# logger.net
KiCad netlist of a schematic drawn in EAGLE
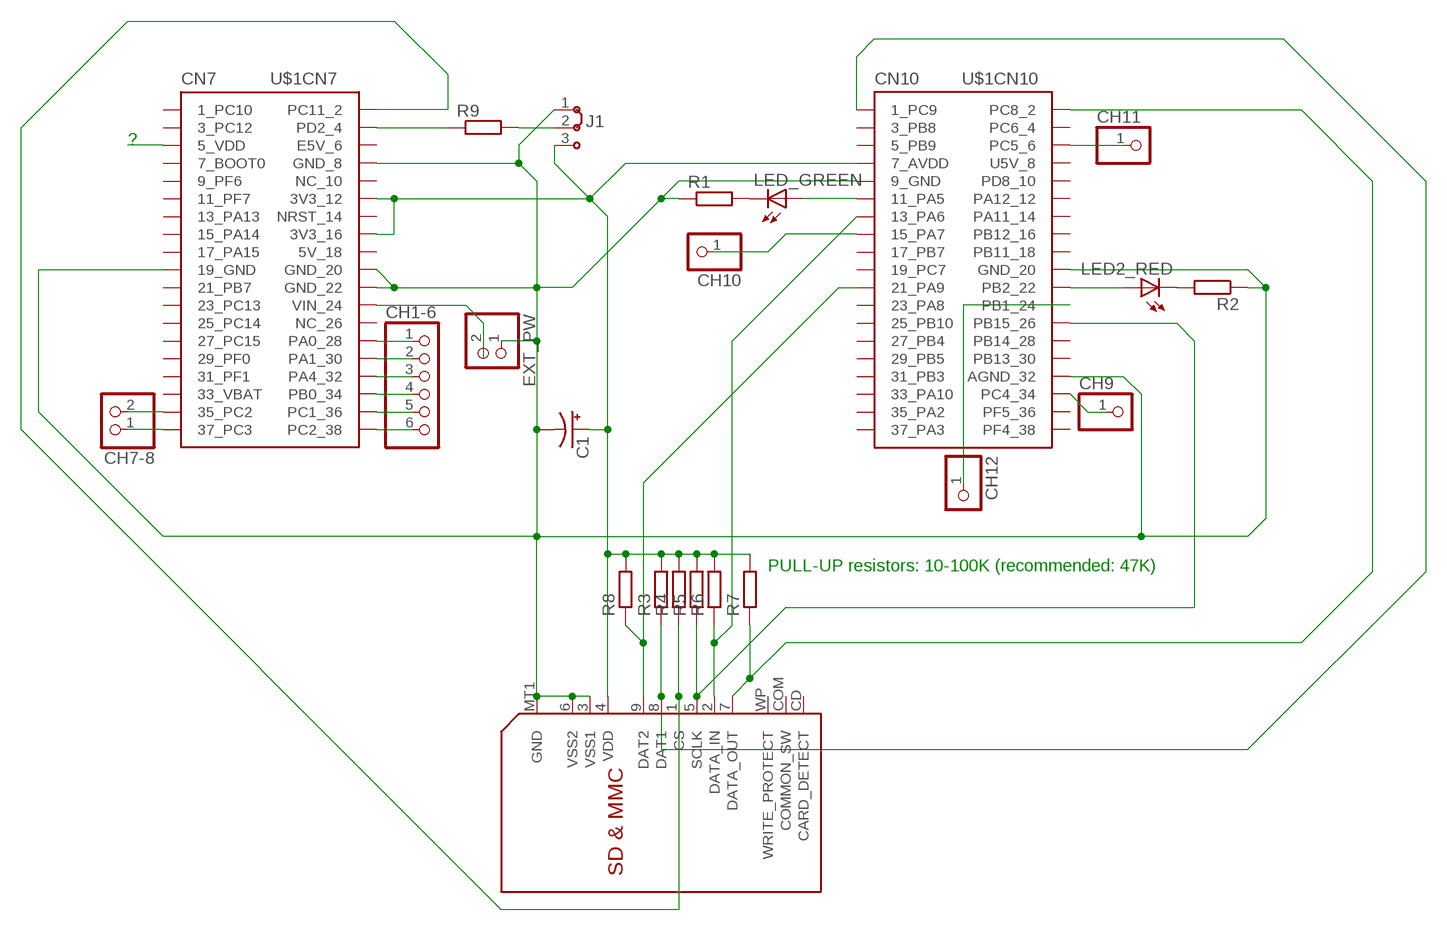
[diagram p0: schematic, sheet 1]

(export (version "E")
  (design (tool "Eeschema 10.0.6"))
  (components
    (comp (ref "C1")
      (value "CPOL-USE5-10.5")
      (footprint "eagle-import:E5-10,5")
      (libsource (lib "eagle-import") (part "CPOL-USE5-10.5"))
    )
    (comp (ref "CH1-6")
      (value "PINHD-1X6B")
      (footprint "eagle-import:1X06-BIG")
      (libsource (lib "eagle-import") (part "PINHD-1X6B"))
    )
    (comp (ref "CH7-8")
      (value "PINHD-1X2")
      (footprint "eagle-import:1X02")
      (libsource (lib "eagle-import") (part "PINHD-1X2"))
    )
    (comp (ref "CH9")
      (value "PINHD-1X1")
      (footprint "eagle-import:1X01")
      (libsource (lib "eagle-import") (part "PINHD-1X1"))
    )
    (comp (ref "CH10")
      (value "PINHD-1X1")
      (footprint "eagle-import:1X01")
      (libsource (lib "eagle-import") (part "PINHD-1X1"))
    )
    (comp (ref "CH11")
      (value "PINHD-1X1")
      (footprint "eagle-import:1X01")
      (libsource (lib "eagle-import") (part "PINHD-1X1"))
    )
    (comp (ref "CH12")
      (value "PINHD-1X1")
      (footprint "eagle-import:1X01")
      (libsource (lib "eagle-import") (part "PINHD-1X1"))
    )
    (comp (ref "EXT_PW")
      (value "PINHD-1X2")
      (footprint "eagle-import:1X02")
      (libsource (lib "eagle-import") (part "PINHD-1X2"))
    )
    (comp (ref "J1")
      (value "J2X2MM")
      (footprint "eagle-import:04C")
      (libsource (lib "eagle-import") (part "J2X2MM"))
    )
    (comp (ref "LED2_RED")
      (value "LED")
      (footprint "eagle-import:SMARTLED-TTW")
      (libsource (lib "eagle-import") (part "LED"))
    )
    (comp (ref "LED_GREEN")
      (value "LED")
      (footprint "eagle-import:SMARTLED-TTW")
      (libsource (lib "eagle-import") (part "LED"))
    )
    (comp (ref "R1")
      (value "R-EU_M3216")
      (footprint "eagle-import:M3216")
      (libsource (lib "eagle-import") (part "R-EU_M3216"))
    )
    (comp (ref "R2")
      (value "R-EU_M3216")
      (footprint "eagle-import:M3216")
      (libsource (lib "eagle-import") (part "R-EU_M3216"))
    )
    (comp (ref "R3")
      (value "R-EU_M3216")
      (footprint "eagle-import:M3216")
      (libsource (lib "eagle-import") (part "R-EU_M3216"))
    )
    (comp (ref "R4")
      (value "R-EU_M3216")
      (footprint "eagle-import:M3216")
      (libsource (lib "eagle-import") (part "R-EU_M3216"))
    )
    (comp (ref "R5")
      (value "R-EU_M3216")
      (footprint "eagle-import:M3216")
      (libsource (lib "eagle-import") (part "R-EU_M3216"))
    )
    (comp (ref "R6")
      (value "R-EU_M3216")
      (footprint "eagle-import:M3216")
      (libsource (lib "eagle-import") (part "R-EU_M3216"))
    )
    (comp (ref "R7")
      (value "R-EU_M3216")
      (footprint "eagle-import:M3216")
      (libsource (lib "eagle-import") (part "R-EU_M3216"))
    )
    (comp (ref "R8")
      (value "R-EU_M3216")
      (footprint "eagle-import:M3216")
      (libsource (lib "eagle-import") (part "R-EU_M3216"))
    )
    (comp (ref "R9")
      (value "R-EU_M3216")
      (footprint "eagle-import:M3216")
      (libsource (lib "eagle-import") (part "R-EU_M3216"))
    )
    (comp (ref "U$1")
      (value "NUCLEO-SHIELD-FULLSIZE")
      (footprint "eagle-import:NUCLEO-SHIELD-WITHHOLES-FULLSIZE")
      (libsource (lib "eagle-import") (part "NUCLEO-SHIELD-FULLSIZE"))
    )
    (comp (ref "U$2")
      (value "SDMMC18650")
      (footprint "eagle-import:SDCARD")
      (libsource (lib "eagle-import") (part "SDMMC18650"))
    )
  )
  (nets
    (net (code "1") (name "Net-(J1-Pad2)") (class "Default")
      (node (ref "J1") (pin "2") (pinfunction "2_2") (pintype "passive"))
      (node (ref "R9") (pin "2") (pinfunction "2_2") (pintype "passive"))
    )
    (net (code "2") (name "Net-(LED2_RED-A)") (class "Default")
      (node (ref "LED2_RED") (pin "A@1") (pinfunction "A_A@1") (pintype "passive"))
      (node (ref "U$1") (pin "CN10_22") (pinfunction "PB2_22_CN10_22") (pintype "bidirectional"))
    )
    (net (code "3") (name "Net-(LED2_RED-C)") (class "Default")
      (node (ref "LED2_RED") (pin "C@1") (pinfunction "C_C@1") (pintype "passive"))
      (node (ref "R2") (pin "2") (pinfunction "2_2") (pintype "passive"))
    )
    (net (code "4") (name "Net-(LED_GREEN-A)") (class "Default")
      (node (ref "LED_GREEN") (pin "A@1") (pinfunction "A_A@1") (pintype "passive"))
      (node (ref "U$1") (pin "CN10_11") (pinfunction "11_PA5_CN10_11") (pintype "bidirectional"))
    )
    (net (code "5") (name "Net-(LED_GREEN-C)") (class "Default")
      (node (ref "LED_GREEN") (pin "C@1") (pinfunction "C_C@1") (pintype "passive"))
      (node (ref "R1") (pin "2") (pinfunction "2_2") (pintype "passive"))
    )
    (net (code "6") (name "Net-(U$1A-7_AVDD)") (class "Default")
      (node (ref "C1") (pin "+") (pinfunction "+_+") (pintype "passive"))
      (node (ref "J1") (pin "3") (pinfunction "3_3") (pintype "passive"))
      (node (ref "R3") (pin "2") (pinfunction "2_2") (pintype "passive"))
      (node (ref "R4") (pin "2") (pinfunction "2_2") (pintype "passive"))
      (node (ref "R5") (pin "2") (pinfunction "2_2") (pintype "passive"))
      (node (ref "R6") (pin "2") (pinfunction "2_2") (pintype "passive"))
      (node (ref "R7") (pin "2") (pinfunction "2_2") (pintype "passive"))
      (node (ref "R8") (pin "2") (pinfunction "2_2") (pintype "passive"))
      (node (ref "U$1") (pin "CN10_7") (pinfunction "7_AVDD_CN10_7") (pintype "bidirectional"))
      (node (ref "U$1") (pin "CN7_12") (pinfunction "3V3_12_CN7_12") (pintype "bidirectional"))
      (node (ref "U$1") (pin "CN7_16") (pinfunction "3V3_16_CN7_16") (pintype "bidirectional"))
      (node (ref "U$2") (pin "4") (pinfunction "VDD_4") (pintype "power_in"))
    )
    (net (code "7") (name "Net-(U$1A-9_GND)") (class "Default")
      (node (ref "C1") (pin "-") (pinfunction "-_-") (pintype "passive"))
      (node (ref "EXT_PW") (pin "1") (pinfunction "1_1") (pintype "passive"))
      (node (ref "J1") (pin "1") (pinfunction "1_1") (pintype "passive"))
      (node (ref "R1") (pin "1") (pinfunction "1_1") (pintype "passive"))
      (node (ref "R2") (pin "1") (pinfunction "1_1") (pintype "passive"))
      (node (ref "U$1") (pin "CN10_20") (pinfunction "GND_20_CN10_20") (pintype "bidirectional"))
      (node (ref "U$1") (pin "CN10_32") (pinfunction "AGND_32_CN10_32") (pintype "bidirectional"))
      (node (ref "U$1") (pin "CN10_9") (pinfunction "9_GND_CN10_9") (pintype "bidirectional"))
      (node (ref "U$1") (pin "CN7_19") (pinfunction "19_GND_CN7_19") (pintype "bidirectional"))
      (node (ref "U$1") (pin "CN7_20") (pinfunction "GND_20_CN7_20") (pintype "bidirectional"))
      (node (ref "U$1") (pin "CN7_22") (pinfunction "GND_22_CN7_22") (pintype "bidirectional"))
      (node (ref "U$1") (pin "CN7_8") (pinfunction "GND_8_CN7_8") (pintype "bidirectional"))
      (node (ref "U$2") (pin "3") (pinfunction "VSS1_3") (pintype "power_in"))
      (node (ref "U$2") (pin "6") (pinfunction "VSS2_6") (pintype "power_in"))
      (node (ref "U$2") (pin "MT1") (pinfunction "GND_MT1") (pintype "power_in"))
    )
    (net (code "8") (name "Net-(U$1A-13_PA6)") (class "Default")
      (node (ref "R6") (pin "1") (pinfunction "1_1") (pintype "passive"))
      (node (ref "U$1") (pin "CN10_13") (pinfunction "13_PA6_CN10_13") (pintype "bidirectional"))
      (node (ref "U$2") (pin "2") (pinfunction "DATA_IN_2") (pintype "input"))
    )
    (net (code "9") (name "Net-(U$1A-15_PA7)") (class "Default")
      (node (ref "CH10") (pin "1") (pinfunction "1_1") (pintype "passive"))
      (node (ref "U$1") (pin "CN10_15") (pinfunction "15_PA7_CN10_15") (pintype "bidirectional"))
    )
    (net (code "10") (name "Net-(U$1A-21_PA9)") (class "Default")
      (node (ref "R8") (pin "1") (pinfunction "1_1") (pintype "passive"))
      (node (ref "U$1") (pin "CN10_21") (pinfunction "21_PA9_CN10_21") (pintype "bidirectional"))
      (node (ref "U$2") (pin "9") (pinfunction "DAT2_9") (pintype "bidirectional"))
    )
    (net (code "11") (name "Net-(U$1A-PB1_24)") (class "Default")
      (node (ref "CH12") (pin "1") (pinfunction "1_1") (pintype "passive"))
      (node (ref "U$1") (pin "CN10_24") (pinfunction "PB1_24_CN10_24") (pintype "bidirectional"))
    )
    (net (code "12") (name "Net-(U$1A-PB15_26)") (class "Default")
      (node (ref "R5") (pin "1") (pinfunction "1_1") (pintype "passive"))
      (node (ref "U$1") (pin "CN10_26") (pinfunction "PB15_26_CN10_26") (pintype "bidirectional"))
      (node (ref "U$2") (pin "5") (pinfunction "SCLK_5") (pintype "input"))
    )
    (net (code "13") (name "Net-(U$1A-PC4_34)") (class "Default")
      (node (ref "CH9") (pin "1") (pinfunction "1_1") (pintype "passive"))
      (node (ref "U$1") (pin "CN10_34") (pinfunction "PC4_34_CN10_34") (pintype "bidirectional"))
    )
    (net (code "14") (name "Net-(U$1A-PC5_6)") (class "Default")
      (node (ref "CH11") (pin "1") (pinfunction "1_1") (pintype "passive"))
      (node (ref "U$1") (pin "CN10_6") (pinfunction "PC5_6_CN10_6") (pintype "bidirectional"))
    )
    (net (code "15") (name "Net-(U$1A-PC8_2)") (class "Default")
      (node (ref "R7") (pin "1") (pinfunction "1_1") (pintype "passive"))
      (node (ref "U$1") (pin "CN10_2") (pinfunction "PC8_2_CN10_2") (pintype "bidirectional"))
      (node (ref "U$2") (pin "7") (pinfunction "DATA_OUT_7") (pintype "output"))
    )
    (net (code "16") (name "Net-(U$1B-35_PC2)") (class "Default")
      (node (ref "CH7-8") (pin "2") (pinfunction "2_2") (pintype "passive"))
      (node (ref "U$1") (pin "CN7_35") (pinfunction "35_PC2_CN7_35") (pintype "bidirectional"))
    )
    (net (code "17") (name "Net-(U$1B-37_PC3)") (class "Default")
      (node (ref "CH7-8") (pin "1") (pinfunction "1_1") (pintype "passive"))
      (node (ref "U$1") (pin "CN7_37") (pinfunction "37_PC3_CN7_37") (pintype "bidirectional"))
    )
    (net (code "18") (name "Net-(U$1B-PA0_28)") (class "Default")
      (node (ref "CH1-6") (pin "1") (pinfunction "1_1") (pintype "passive"))
      (node (ref "U$1") (pin "CN7_28") (pinfunction "PA0_28_CN7_28") (pintype "bidirectional"))
    )
    (net (code "19") (name "Net-(U$1B-PA1_30)") (class "Default")
      (node (ref "CH1-6") (pin "2") (pinfunction "2_2") (pintype "passive"))
      (node (ref "U$1") (pin "CN7_30") (pinfunction "PA1_30_CN7_30") (pintype "bidirectional"))
    )
    (net (code "20") (name "Net-(U$1B-PA4_32)") (class "Default")
      (node (ref "CH1-6") (pin "3") (pinfunction "3_3") (pintype "passive"))
      (node (ref "U$1") (pin "CN7_32") (pinfunction "PA4_32_CN7_32") (pintype "bidirectional"))
    )
    (net (code "21") (name "Net-(U$1B-PB0_34)") (class "Default")
      (node (ref "CH1-6") (pin "4") (pinfunction "4_4") (pintype "passive"))
      (node (ref "U$1") (pin "CN7_34") (pinfunction "PB0_34_CN7_34") (pintype "bidirectional"))
    )
    (net (code "22") (name "Net-(U$1B-PC1_36)") (class "Default")
      (node (ref "CH1-6") (pin "5") (pinfunction "5_5") (pintype "passive"))
      (node (ref "U$1") (pin "CN7_36") (pinfunction "PC1_36_CN7_36") (pintype "bidirectional"))
    )
    (net (code "23") (name "Net-(U$1B-PC2_38)") (class "Default")
      (node (ref "CH1-6") (pin "6") (pinfunction "6_6") (pintype "passive"))
      (node (ref "U$1") (pin "CN7_38") (pinfunction "PC2_38_CN7_38") (pintype "bidirectional"))
    )
    (net (code "24") (name "Net-(U$1B-PC11_2)") (class "Default")
      (node (ref "R4") (pin "1") (pinfunction "1_1") (pintype "passive"))
      (node (ref "U$1") (pin "CN7_2") (pinfunction "PC11_2_CN7_2") (pintype "bidirectional"))
      (node (ref "U$2") (pin "1") (pinfunction "CS_1") (pintype "input"))
    )
    (net (code "25") (name "Net-(U$1B-PD2_4)") (class "Default")
      (node (ref "R9") (pin "1") (pinfunction "1_1") (pintype "passive"))
      (node (ref "U$1") (pin "CN7_4") (pinfunction "PD2_4_CN7_4") (pintype "bidirectional"))
    )
    (net (code "26") (name "Net-(U$2-DAT1)") (class "Default")
      (node (ref "R3") (pin "1") (pinfunction "1_1") (pintype "passive"))
      (node (ref "U$2") (pin "8") (pinfunction "DAT1_8") (pintype "bidirectional"))
    )
    (net (code "27") (name "unconnected-(EXT_PW-Pad2)") (class "Default")
      (node (ref "EXT_PW") (pin "2") (pinfunction "2_2") (pintype "passive"))
    )
    (net (code "28") (name "unconnected-(U$1A-1_PC9-PadCN10_1)") (class "Default")
      (node (ref "U$1") (pin "CN10_1") (pinfunction "1_PC9_CN10_1") (pintype "bidirectional"))
    )
    (net (code "29") (name "unconnected-(U$1A-3_PB8-PadCN10_3)") (class "Default")
      (node (ref "U$1") (pin "CN10_3") (pinfunction "3_PB8_CN10_3") (pintype "bidirectional"))
    )
    (net (code "30") (name "unconnected-(U$1A-5_PB9-PadCN10_5)") (class "Default")
      (node (ref "U$1") (pin "CN10_5") (pinfunction "5_PB9_CN10_5") (pintype "bidirectional"))
    )
    (net (code "31") (name "unconnected-(U$1A-17_PB7-PadCN10_17)") (class "Default")
      (node (ref "U$1") (pin "CN10_17") (pinfunction "17_PB7_CN10_17") (pintype "bidirectional"))
    )
    (net (code "32") (name "unconnected-(U$1A-19_PC7-PadCN10_19)") (class "Default")
      (node (ref "U$1") (pin "CN10_19") (pinfunction "19_PC7_CN10_19") (pintype "bidirectional"))
    )
    (net (code "33") (name "unconnected-(U$1A-23_PA8-PadCN10_23)") (class "Default")
      (node (ref "U$1") (pin "CN10_23") (pinfunction "23_PA8_CN10_23") (pintype "bidirectional"))
    )
    (net (code "34") (name "unconnected-(U$1A-25_PB10-PadCN10_25)") (class "Default")
      (node (ref "U$1") (pin "CN10_25") (pinfunction "25_PB10_CN10_25") (pintype "bidirectional"))
    )
    (net (code "35") (name "unconnected-(U$1A-27_PB4-PadCN10_27)") (class "Default")
      (node (ref "U$1") (pin "CN10_27") (pinfunction "27_PB4_CN10_27") (pintype "bidirectional"))
    )
    (net (code "36") (name "unconnected-(U$1A-29_PB5-PadCN10_29)") (class "Default")
      (node (ref "U$1") (pin "CN10_29") (pinfunction "29_PB5_CN10_29") (pintype "bidirectional"))
    )
    (net (code "37") (name "unconnected-(U$1A-31_PB3-PadCN10_31)") (class "Default")
      (node (ref "U$1") (pin "CN10_31") (pinfunction "31_PB3_CN10_31") (pintype "bidirectional"))
    )
    (net (code "38") (name "unconnected-(U$1A-33_PA10-PadCN10_33)") (class "Default")
      (node (ref "U$1") (pin "CN10_33") (pinfunction "33_PA10_CN10_33") (pintype "bidirectional"))
    )
    (net (code "39") (name "unconnected-(U$1A-35_PA2-PadCN10_35)") (class "Default")
      (node (ref "U$1") (pin "CN10_35") (pinfunction "35_PA2_CN10_35") (pintype "bidirectional"))
    )
    (net (code "40") (name "unconnected-(U$1A-37_PA3-PadCN10_37)") (class "Default")
      (node (ref "U$1") (pin "CN10_37") (pinfunction "37_PA3_CN10_37") (pintype "bidirectional"))
    )
    (net (code "41") (name "unconnected-(U$1A-PA11_14-PadCN10_14)") (class "Default")
      (node (ref "U$1") (pin "CN10_14") (pinfunction "PA11_14_CN10_14") (pintype "bidirectional"))
    )
    (net (code "42") (name "unconnected-(U$1A-PA12_12-PadCN10_12)") (class "Default")
      (node (ref "U$1") (pin "CN10_12") (pinfunction "PA12_12_CN10_12") (pintype "bidirectional"))
    )
    (net (code "43") (name "unconnected-(U$1A-PB11_18-PadCN10_18)") (class "Default")
      (node (ref "U$1") (pin "CN10_18") (pinfunction "PB11_18_CN10_18") (pintype "bidirectional"))
    )
    (net (code "44") (name "unconnected-(U$1A-PB12_16-PadCN10_16)") (class "Default")
      (node (ref "U$1") (pin "CN10_16") (pinfunction "PB12_16_CN10_16") (pintype "bidirectional"))
    )
    (net (code "45") (name "unconnected-(U$1A-PB13_30-PadCN10_30)") (class "Default")
      (node (ref "U$1") (pin "CN10_30") (pinfunction "PB13_30_CN10_30") (pintype "bidirectional"))
    )
    (net (code "46") (name "unconnected-(U$1A-PB14_28-PadCN10_28)") (class "Default")
      (node (ref "U$1") (pin "CN10_28") (pinfunction "PB14_28_CN10_28") (pintype "bidirectional"))
    )
    (net (code "47") (name "unconnected-(U$1A-PC6_4-PadCN10_4)") (class "Default")
      (node (ref "U$1") (pin "CN10_4") (pinfunction "PC6_4_CN10_4") (pintype "bidirectional"))
    )
    (net (code "48") (name "unconnected-(U$1A-PD8_10-PadCN10_10)") (class "Default")
      (node (ref "U$1") (pin "CN10_10") (pinfunction "PD8_10_CN10_10") (pintype "bidirectional"))
    )
    (net (code "49") (name "unconnected-(U$1A-PF4_38-PadCN10_38)") (class "Default")
      (node (ref "U$1") (pin "CN10_38") (pinfunction "PF4_38_CN10_38") (pintype "bidirectional"))
    )
    (net (code "50") (name "unconnected-(U$1A-PF5_36-PadCN10_36)") (class "Default")
      (node (ref "U$1") (pin "CN10_36") (pinfunction "PF5_36_CN10_36") (pintype "bidirectional"))
    )
    (net (code "51") (name "unconnected-(U$1A-U5V_8-PadCN10_8)") (class "Default")
      (node (ref "U$1") (pin "CN10_8") (pinfunction "U5V_8_CN10_8") (pintype "bidirectional"))
    )
    (net (code "52") (name "unconnected-(U$1B-1_PC10-PadCN7_1)") (class "Default")
      (node (ref "U$1") (pin "CN7_1") (pinfunction "1_PC10_CN7_1") (pintype "bidirectional"))
    )
    (net (code "53") (name "unconnected-(U$1B-3_PC12-PadCN7_3)") (class "Default")
      (node (ref "U$1") (pin "CN7_3") (pinfunction "3_PC12_CN7_3") (pintype "bidirectional"))
    )
    (net (code "54") (name "unconnected-(U$1B-5V_18-PadCN7_18)") (class "Default")
      (node (ref "U$1") (pin "CN7_18") (pinfunction "5V_18_CN7_18") (pintype "bidirectional"))
    )
    (net (code "55") (name "unconnected-(U$1B-5_VDD-PadCN7_5)") (class "Default")
      (node (ref "U$1") (pin "CN7_5") (pinfunction "5_VDD_CN7_5") (pintype "bidirectional"))
    )
    (net (code "56") (name "unconnected-(U$1B-7_BOOT0-PadCN7_7)") (class "Default")
      (node (ref "U$1") (pin "CN7_7") (pinfunction "7_BOOT0_CN7_7") (pintype "bidirectional"))
    )
    (net (code "57") (name "unconnected-(U$1B-9_PF6-PadCN7_9)") (class "Default")
      (node (ref "U$1") (pin "CN7_9") (pinfunction "9_PF6_CN7_9") (pintype "bidirectional"))
    )
    (net (code "58") (name "unconnected-(U$1B-11_PF7-PadCN7_11)") (class "Default")
      (node (ref "U$1") (pin "CN7_11") (pinfunction "11_PF7_CN7_11") (pintype "bidirectional"))
    )
    (net (code "59") (name "unconnected-(U$1B-13_PA13-PadCN7_13)") (class "Default")
      (node (ref "U$1") (pin "CN7_13") (pinfunction "13_PA13_CN7_13") (pintype "bidirectional"))
    )
    (net (code "60") (name "unconnected-(U$1B-15_PA14-PadCN7_15)") (class "Default")
      (node (ref "U$1") (pin "CN7_15") (pinfunction "15_PA14_CN7_15") (pintype "bidirectional"))
    )
    (net (code "61") (name "unconnected-(U$1B-17_PA15-PadCN7_17)") (class "Default")
      (node (ref "U$1") (pin "CN7_17") (pinfunction "17_PA15_CN7_17") (pintype "bidirectional"))
    )
    (net (code "62") (name "unconnected-(U$1B-21_PB7-PadCN7_21)") (class "Default")
      (node (ref "U$1") (pin "CN7_21") (pinfunction "21_PB7_CN7_21") (pintype "bidirectional"))
    )
    (net (code "63") (name "unconnected-(U$1B-23_PC13-PadCN7_23)") (class "Default")
      (node (ref "U$1") (pin "CN7_23") (pinfunction "23_PC13_CN7_23") (pintype "bidirectional"))
    )
    (net (code "64") (name "unconnected-(U$1B-25_PC14-PadCN7_25)") (class "Default")
      (node (ref "U$1") (pin "CN7_25") (pinfunction "25_PC14_CN7_25") (pintype "bidirectional"))
    )
    (net (code "65") (name "unconnected-(U$1B-27_PC15-PadCN7_27)") (class "Default")
      (node (ref "U$1") (pin "CN7_27") (pinfunction "27_PC15_CN7_27") (pintype "bidirectional"))
    )
    (net (code "66") (name "unconnected-(U$1B-29_PF0-PadCN7_29)") (class "Default")
      (node (ref "U$1") (pin "CN7_29") (pinfunction "29_PF0_CN7_29") (pintype "bidirectional"))
    )
    (net (code "67") (name "unconnected-(U$1B-31_PF1-PadCN7_31)") (class "Default")
      (node (ref "U$1") (pin "CN7_31") (pinfunction "31_PF1_CN7_31") (pintype "bidirectional"))
    )
    (net (code "68") (name "unconnected-(U$1B-33_VBAT-PadCN7_33)") (class "Default")
      (node (ref "U$1") (pin "CN7_33") (pinfunction "33_VBAT_CN7_33") (pintype "bidirectional"))
    )
    (net (code "69") (name "unconnected-(U$1B-E5V_6-PadCN7_6)") (class "Default")
      (node (ref "U$1") (pin "CN7_6") (pinfunction "E5V_6_CN7_6") (pintype "bidirectional"))
    )
    (net (code "70") (name "unconnected-(U$1B-NC_10-PadCN7_10)") (class "Default")
      (node (ref "U$1") (pin "CN7_10") (pinfunction "NC_10_CN7_10") (pintype "bidirectional"))
    )
    (net (code "71") (name "unconnected-(U$1B-NC_26-PadCN7_26)") (class "Default")
      (node (ref "U$1") (pin "CN7_26") (pinfunction "NC_26_CN7_26") (pintype "bidirectional"))
    )
    (net (code "72") (name "unconnected-(U$1B-NRST_14-PadCN7_14)") (class "Default")
      (node (ref "U$1") (pin "CN7_14") (pinfunction "NRST_14_CN7_14") (pintype "bidirectional"))
    )
    (net (code "73") (name "unconnected-(U$1B-VIN_24-PadCN7_24)") (class "Default")
      (node (ref "U$1") (pin "CN7_24") (pinfunction "VIN_24_CN7_24") (pintype "bidirectional"))
    )
    (net (code "74") (name "unconnected-(U$2-CARD_DETECT-PadCD)") (class "Default")
      (node (ref "U$2") (pin "CD") (pinfunction "CARD_DETECT_CD") (pintype "passive"))
    )
    (net (code "75") (name "unconnected-(U$2-COMMON_SW-PadCOM)") (class "Default")
      (node (ref "U$2") (pin "COM") (pinfunction "COMMON_SW_COM") (pintype "passive"))
    )
    (net (code "76") (name "unconnected-(U$2-WRITE_PROTECT-PadWP)") (class "Default")
      (node (ref "U$2") (pin "WP") (pinfunction "WRITE_PROTECT_WP") (pintype "passive"))
    )
  )
)
